# bq_RepRap_LCD_SmartController_ConAdap.net
KiCad netlist of a schematic drawn in Altium Designer
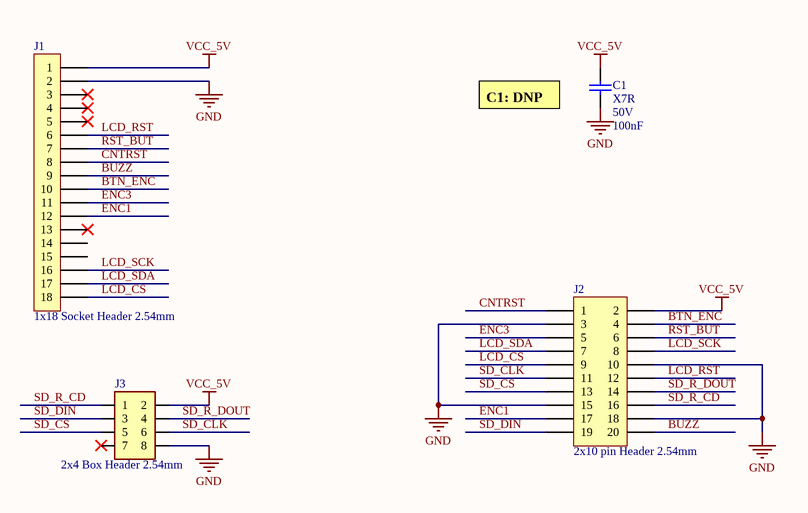
[diagram p0: bq RepRap LCD SmartController_ConAdap.SchDoc]

(export (version "E")
  (design (tool "Eeschema 10.0.6"))
  (components
    (comp (ref "C1")
      (value "Capacitor")
      (footprint "CAP5,50x3,50")
      (fields
        (field (name "DIELECTRIC") "X7R")
        (field (name "VOLTAGE") "50V")
        (field (name "CAPACITANCE") "100nF")
        (field (name "PART NUMBER") "100nF_50V_±10%")
        (field (name "TOLERANCE") "±10%")
        (field (name "MANUFACTURER") "Kemet")
      )
      (libsource (lib "Pasives_Capacitor_THT") (part "Capacitor"))
    )
    (comp (ref "J1")
      (value "1x18 Socket Header 2.54mm")
      (footprint "1x18 Socket Header THT 2.54mm")
      (description "Connector, 18 pin Socket Header 2.54mm")
      (fields (field (name "MANUFACTURER") "Samtec") (field (name "PART NUMBER") "CON_SH_THT2.54_18"))
      (libsource (lib "Conectores_SocketHeader_2.54") (part "1x18 Socket Header 2.54mm"))
    )
    (comp (ref "J2")
      (value "2x10 pin Header 2.54mm")
      (footprint "2x10 pin Header 2.54")
      (description "20 pin Dual Header 2.54mm")
      (fields (field (name "MANUFACTURER") "Samtec") (field (name "PART NUMBER") "CON_DPH_THT2.54_20"))
      (libsource (lib "Conectores_PinHeader_2.54") (part "2x10 pin Header 2.54mm"))
    )
    (comp (ref "J3")
      (value "2x4 Box Header 2.54mm")
      (footprint "2x4 Box Header THD 2.54mm")
      (description "Connector, 8 Pin Box Dual Header 2.54mm")
      (fields (field (name "MANUFACTURER") "Samtec") (field (name "PART NUMBER") "CON_DBH_THD_2.54_8"))
      (libsource (lib "Connectors_BoxHeader_2.54") (part "2x4 Box Header 2.54mm"))
    )
  )
  (nets
    (net (code "1") (name "/BTN_ENC") (class "Default")
      (node (ref "J1") (pin "10") (pinfunction "10_10") (pintype "power_in"))
      (node (ref "J2") (pin "4") (pinfunction "4_4") (pintype "passive"))
    )
    (net (code "2") (name "/BUZZ") (class "Default")
      (node (ref "J1") (pin "9") (pinfunction "9_9") (pintype "power_in"))
      (node (ref "J2") (pin "20") (pinfunction "20_20") (pintype "passive"))
    )
    (net (code "3") (name "/CNTRST") (class "Default")
      (node (ref "J1") (pin "8") (pinfunction "8_8") (pintype "passive"))
      (node (ref "J2") (pin "1") (pinfunction "1_1") (pintype "passive"))
    )
    (net (code "4") (name "/ENC1") (class "Default")
      (node (ref "J1") (pin "12") (pinfunction "12_12") (pintype "power_in"))
      (node (ref "J2") (pin "17") (pinfunction "17_17") (pintype "power_in"))
    )
    (net (code "5") (name "/ENC3") (class "Default")
      (node (ref "J1") (pin "11") (pinfunction "11_11") (pintype "power_in"))
      (node (ref "J2") (pin "5") (pinfunction "5_5") (pintype "passive"))
    )
    (net (code "6") (name "/LCD_CS") (class "Default")
      (node (ref "J1") (pin "18") (pinfunction "18_18") (pintype "power_in"))
      (node (ref "J2") (pin "9") (pinfunction "9_9") (pintype "passive"))
    )
    (net (code "7") (name "/LCD_RST") (class "Default")
      (node (ref "J1") (pin "6") (pinfunction "6_6") (pintype "passive"))
      (node (ref "J2") (pin "12") (pinfunction "12_12") (pintype "passive"))
    )
    (net (code "8") (name "/LCD_SCK") (class "Default")
      (node (ref "J1") (pin "16") (pinfunction "16_16") (pintype "power_in"))
      (node (ref "J2") (pin "8") (pinfunction "8_8") (pintype "passive"))
    )
    (net (code "9") (name "/LCD_SDA") (class "Default")
      (node (ref "J1") (pin "17") (pinfunction "17_17") (pintype "power_in"))
      (node (ref "J2") (pin "7") (pinfunction "7_7") (pintype "passive"))
    )
    (net (code "10") (name "/RST_BUT") (class "Default")
      (node (ref "J1") (pin "7") (pinfunction "7_7") (pintype "passive"))
      (node (ref "J2") (pin "6") (pinfunction "6_6") (pintype "passive"))
    )
    (net (code "11") (name "/SD_CLK") (class "Default")
      (node (ref "J2") (pin "11") (pinfunction "11_11") (pintype "passive"))
      (node (ref "J3") (pin "6") (pinfunction "6_6") (pintype "passive"))
    )
    (net (code "12") (name "/SD_CS") (class "Default")
      (node (ref "J2") (pin "13") (pinfunction "13_13") (pintype "passive"))
      (node (ref "J3") (pin "5") (pinfunction "5_5") (pintype "passive"))
    )
    (net (code "13") (name "/SD_DIN") (class "Default")
      (node (ref "J2") (pin "19") (pinfunction "19_19") (pintype "passive"))
      (node (ref "J3") (pin "3") (pinfunction "3_3") (pintype "passive"))
    )
    (net (code "14") (name "/SD_R_CD") (class "Default")
      (node (ref "J2") (pin "16") (pinfunction "16_16") (pintype "passive"))
      (node (ref "J3") (pin "1") (pinfunction "1_1") (pintype "passive"))
    )
    (net (code "15") (name "/SD_R_DOUT") (class "Default")
      (node (ref "J2") (pin "14") (pinfunction "14_14") (pintype "passive"))
      (node (ref "J3") (pin "4") (pinfunction "4_4") (pintype "passive"))
    )
    (net (code "16") (name "GND") (class "Default")
      (node (ref "C1") (pin "1") (pinfunction "1_1") (pintype "passive"))
      (node (ref "J1") (pin "2") (pinfunction "2_2") (pintype "passive"))
      (node (ref "J2") (pin "10") (pinfunction "10_10") (pintype "passive"))
      (node (ref "J2") (pin "15") (pinfunction "15_15") (pintype "passive"))
      (node (ref "J2") (pin "18") (pinfunction "18_18") (pintype "power_in"))
      (node (ref "J2") (pin "3") (pinfunction "3_3") (pintype "passive"))
      (node (ref "J3") (pin "8") (pinfunction "8_8") (pintype "passive"))
    )
    (net (code "17") (name "VCC_5V") (class "Default")
      (node (ref "C1") (pin "2") (pinfunction "2_2") (pintype "passive"))
      (node (ref "J1") (pin "1") (pinfunction "1_1") (pintype "passive"))
      (node (ref "J2") (pin "2") (pinfunction "2_2") (pintype "passive"))
      (node (ref "J3") (pin "2") (pinfunction "2_2") (pintype "passive"))
    )
    (net (code "18") (name "unconnected-(J1-Pad3)") (class "Default")
      (node (ref "J1") (pin "3") (pinfunction "3_3") (pintype "passive+no_connect"))
    )
    (net (code "19") (name "unconnected-(J1-Pad4)") (class "Default")
      (node (ref "J1") (pin "4") (pinfunction "4_4") (pintype "passive+no_connect"))
    )
    (net (code "20") (name "unconnected-(J1-Pad5)") (class "Default")
      (node (ref "J1") (pin "5") (pinfunction "5_5") (pintype "passive+no_connect"))
    )
    (net (code "21") (name "unconnected-(J1-Pad13)") (class "Default")
      (node (ref "J1") (pin "13") (pinfunction "13_13") (pintype "power_in+no_connect"))
    )
    (net (code "22") (name "unconnected-(J1-Pad14)") (class "Default")
      (node (ref "J1") (pin "14") (pinfunction "14_14") (pintype "power_in"))
    )
    (net (code "23") (name "unconnected-(J1-Pad15)") (class "Default")
      (node (ref "J1") (pin "15") (pinfunction "15_15") (pintype "power_in"))
    )
    (net (code "24") (name "unconnected-(J3-Pad7)") (class "Default")
      (node (ref "J3") (pin "7") (pinfunction "7_7") (pintype "passive+no_connect"))
    )
  )
)
